# Sheet_V2.net
KiCad netlist of a schematic drawn in Altium Designer
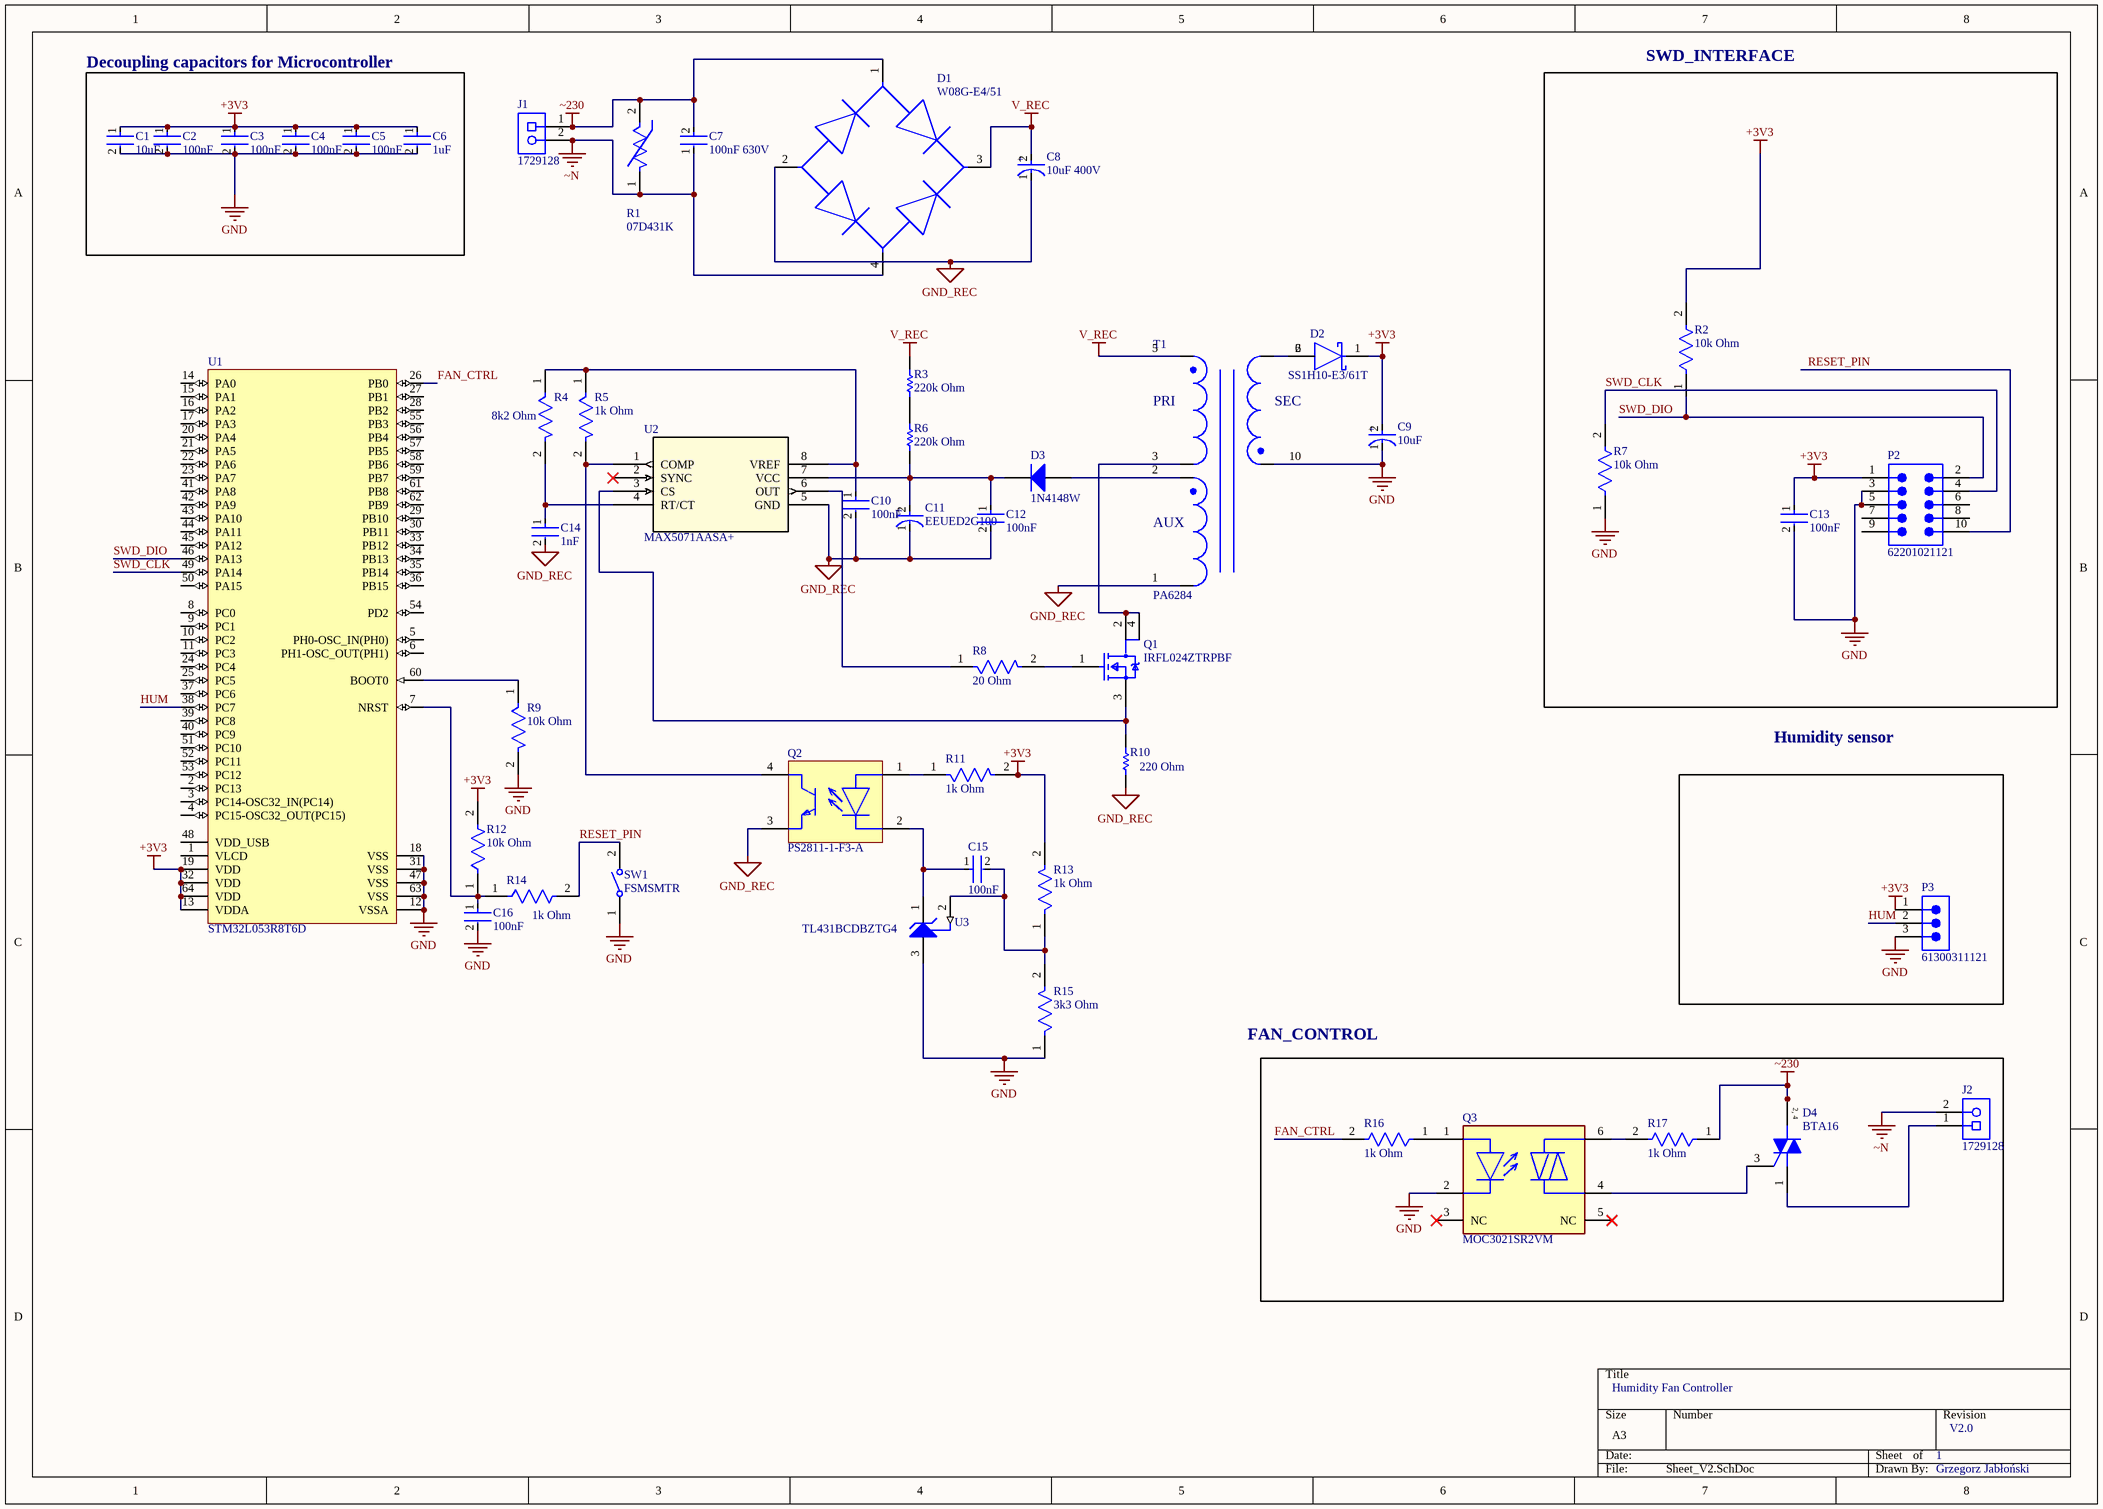
[diagram p0: Sheet_V2.SchDoc]

(export (version "E")
  (design (tool "Eeschema 10.0.6"))
  (components
    (comp (ref "C1")
      (value "10uF")
      (footprint "FP-CC0805-0_85-MFG")
      (description "CAP CER 0.1UF 50V X7R 0805")
      (fields (field (name "TOLERANCE") "0.1") (field (name "MANUFACTURER PART NUMBER") "CC0805KRX7R9BB104"))
      (libsource (lib "Altium Content Vault") (part "11868f565c42a9108669ba33697ecf6"))
    )
    (comp (ref "C2")
      (value "100nF")
      (footprint "FP-CC0805-0_85-MFG")
      (description "CAP CER 0.1UF 50V X7R 0805")
      (fields (field (name "TOLERANCE") "0.1") (field (name "MANUFACTURER PART NUMBER") "CC0805KRX7R9BB104"))
      (libsource (lib "Altium Content Vault") (part "11868f565c42a9108669ba33697ecf6"))
    )
    (comp (ref "C3")
      (value "100nF")
      (footprint "FP-CC0805-0_85-MFG")
      (description "CAP CER 0.1UF 50V X7R 0805")
      (fields (field (name "TOLERANCE") "0.1") (field (name "MANUFACTURER PART NUMBER") "CC0805KRX7R9BB104"))
      (libsource (lib "Altium Content Vault") (part "11868f565c42a9108669ba33697ecf6"))
    )
    (comp (ref "C4")
      (value "100nF")
      (footprint "FP-CC0805-0_85-MFG")
      (description "CAP CER 0.1UF 50V X7R 0805")
      (fields (field (name "TOLERANCE") "0.1") (field (name "MANUFACTURER PART NUMBER") "CC0805KRX7R9BB104"))
      (libsource (lib "Altium Content Vault") (part "11868f565c42a9108669ba33697ecf6"))
    )
    (comp (ref "C5")
      (value "100nF")
      (footprint "FP-CC0805-0_85-MFG")
      (description "CAP CER 0.1UF 50V X7R 0805")
      (fields (field (name "TOLERANCE") "0.1") (field (name "MANUFACTURER PART NUMBER") "CC0805KRX7R9BB104"))
      (libsource (lib "Altium Content Vault") (part "11868f565c42a9108669ba33697ecf6"))
    )
    (comp (ref "C6")
      (value "1uF")
      (footprint "FP-CC0805-0_85-MFG")
      (description "CAP CER 0.1UF 50V X7R 0805")
      (fields (field (name "TOLERANCE") "0.1") (field (name "MANUFACTURER PART NUMBER") "CC0805KRX7R9BB104"))
      (libsource (lib "Altium Content Vault") (part "11868f565c42a9108669ba33697ecf6"))
    )
    (comp (ref "C7")
      (value "100nF 630V")
      (footprint "FP-BFC233620104-MFG")
      (description "CAP FILM 0.1UF 20% 630VDC RADIAL")
      (fields (field (name "VOLTAGE") "250V") (field (name "TOLERANCE") "20%"))
      (libsource (lib "Altium Content Vault") (part "236180d848d6139a670b325ea6854c9"))
    )
    (comp (ref "C8")
      (value "10uF 400V")
      (footprint "FP-RAD-TH-D_10_0_5-L_20_2-MFG")
      (description "Aluminum Electrolytic Capacitors (Radial Lead Type) 10uF ±20% 400V")
      (fields (field (name "VOLTAGE") "400V") (field (name "TOLERANCE") "20%"))
      (libsource (lib "Altium Content Vault") (part "203bc49f2ac43e59fd269a8c329ed05"))
    )
    (comp (ref "C9")
      (value "10uF")
      (footprint "FP-RAD-TH-D_6_3_0_5-L_7_1-MFG")
      (description "Aluminum Electrolytic Capacitors (Radial Lead Type) 15uF ±20% 35V")
      (fields (field (name "TOLERANCE") "20%") (field (name "VOLTAGE") "35V"))
      (libsource (lib "Altium Content Vault") (part "a00bbbee19879c290e62620ae7e47b1"))
    )
    (comp (ref "C10")
      (value "100nF")
      (footprint "FP-CC0805-0_85-MFG")
      (description "CAP CER 0.1UF 50V X7R 0805")
      (fields (field (name "TOLERANCE") "0.1") (field (name "MANUFACTURER PART NUMBER") "CC0805KRX7R9BB104"))
      (libsource (lib "Altium Content Vault") (part "11868f565c42a9108669ba33697ecf6"))
    )
    (comp (ref "C11")
      (value "EEUED2G100")
      (footprint "FP-RAD-TH-D_10_0_5-L_20_2-MFG")
      (description "Aluminum Electrolytic Capacitors (Radial Lead Type) 10uF ±20% 400V")
      (fields (field (name "VOLTAGE") "400V") (field (name "TOLERANCE") "20%"))
      (libsource (lib "Altium Content Vault") (part "203bc49f2ac43e59fd269a8c329ed05"))
    )
    (comp (ref "C12")
      (value "100nF")
      (footprint "FP-CC0805-0_85-MFG")
      (description "CAP CER 0.1UF 50V X7R 0805")
      (fields (field (name "TOLERANCE") "0.1") (field (name "MANUFACTURER PART NUMBER") "CC0805KRX7R9BB104"))
      (libsource (lib "Altium Content Vault") (part "11868f565c42a9108669ba33697ecf6"))
    )
    (comp (ref "C13")
      (value "100nF")
      (footprint "FP-CC0805-0_85-MFG")
      (description "CAP CER 0.1UF 50V X7R 0805")
      (fields (field (name "TOLERANCE") "0.1") (field (name "MANUFACTURER PART NUMBER") "CC0805KRX7R9BB104"))
      (libsource (lib "Altium Content Vault") (part "11868f565c42a9108669ba33697ecf6"))
    )
    (comp (ref "C14")
      (value "1nF")
      (footprint "FP-CC0805-0_85-MFG")
      (description "CAP CER 0.1UF 50V X7R 0805")
      (fields (field (name "TOLERANCE") "0.1") (field (name "MANUFACTURER PART NUMBER") "CC0805KRX7R9BB104"))
      (libsource (lib "Altium Content Vault") (part "11868f565c42a9108669ba33697ecf6"))
    )
    (comp (ref "C15")
      (value "100nF")
      (footprint "FP-CC0805-0_85-MFG")
      (description "CAP CER 0.1UF 50V X7R 0805")
      (fields (field (name "TOLERANCE") "0.1") (field (name "MANUFACTURER PART NUMBER") "CC0805KRX7R9BB104"))
      (libsource (lib "Altium Content Vault") (part "11868f565c42a9108669ba33697ecf6"))
    )
    (comp (ref "C16")
      (value "100nF")
      (footprint "FP-CC0805-0_85-MFG")
      (description "CAP CER 0.1UF 50V X7R 0805")
      (fields (field (name "TOLERANCE") "0.1") (field (name "MANUFACTURER PART NUMBER") "CC0805KRX7R9BB104"))
      (libsource (lib "Altium Content Vault") (part "11868f565c42a9108669ba33697ecf6"))
    )
    (comp (ref "D1")
      (value "W08G-E4/51")
      (footprint "FP-WOG-MFG")
      (description "W08G-E4/51 Diode Rectifier Bridge Single 800V 1.5A 4-Pin Case WOG Bulk")
      (libsource (lib "Altium Content Vault") (part "7f679ecdc54638986ed3433d0c5b104"))
    )
    (comp (ref "D2")
      (value "SS1H10-E3/61T")
      (footprint "FP-95400-MFG")
      (description "DIODE SCHOTTKY 100V 1A DO214AC")
      (fields
        (field (name "OCTOPART") "https://octopart.com/ss1h10-e3%2F61t-vishay-39552861")
        (field (name "MANUFACTURER") "Vishay")
      )
      (libsource (lib "Altium Content Vault") (part "1d6ec82d83fb6aee721767c19dac4b9"))
    )
    (comp (ref "D3")
      (value "1N4148W")
      (footprint "DIOD-SOD123-2_V")
      (description "Fast Switching Diode, 100 V, 0.15 A, -65 to 150 degC, 2-Pin?SOD123, RoHS, Tape and Reel")
      (fields (field (name "MANUFACTURER") "DiodesIncorporated"))
      (libsource (lib "Altium Content Vault") (part "D-AK-2"))
    )
    (comp (ref "D4")
      (value "BTA16")
      (footprint "ONSC-SOT-223-4-318E-04_V")
      (fields (field (name "MANUFACTURER") "On Semiconductor") (field (name "PARTNUMBER") "Z0107MNT1G"))
      (libsource (lib "Altium Content Vault") (part "ONSC-TRIAC-MT1MT2GMT2-4"))
    )
    (comp (ref "J1")
      (value "1729128")
      (footprint "PHOE-1729128-2_V")
      (description "PCB Terminal Block, 13.5 A, 400 V, 2-Pin THD, RoHS, Bulk")
      (fields (field (name "MANUFACTURER") "Phoenix Contact"))
      (libsource (lib "") (part "CN-2P-F-R2_1"))
    )
    (comp (ref "J2")
      (value "1729128")
      (footprint "PHOE-1729128-2_V")
      (description "PCB Terminal Block, 13.5 A, 400 V, 2-Pin THD, RoHS, Bulk")
      (fields (field (name "MANUFACTURER") "Phoenix Contact"))
      (libsource (lib "Altium Content Vault") (part "CN-2P-F-R2"))
    )
    (comp (ref "P2")
      (value "62201021121")
      (footprint "62201021121")
      (libsource (lib "Altium Content Vault") (part "Header_Male_2R_10P"))
    )
    (comp (ref "P3")
      (value "61300311121")
      (footprint "61300311121")
      (libsource (lib "Altium Content Vault") (part "Header_Male_1R_03P"))
    )
    (comp (ref "Q1")
      (value "IRFL024ZTRPBF")
      (footprint "FP-PG-SOT223-3-MFG")
      (description "MOSFET N-CH 55V 5.1A SOT223")
      (libsource (lib "Altium Content Vault") (part "c6745a01100a3e91667466909d2f9ef"))
    )
    (comp (ref "Q2")
      (value "PS2811-1-F3-A")
      (footprint "SOP127P700X210_HS-5_SO4-Opto2_N")
      (description "Optocoupler DC-IN 1-CH Transistor DC-OUT 4-Pin SSOP Embossed T/R")
      (libsource (lib "Altium Content Vault") (part "f4732c5a005c16655bf03302f8bd1cc"))
    )
    (comp (ref "Q3")
      (value "MOC3021SR2VM")
      (footprint "FP-646BY-MFG")
      (description "MOC3021SR2VM Triac Driver Output Optocoupler, 6-Pin DIP 400V Random Phase")
      (libsource (lib "Altium Content Vault") (part "315d33d7a3de83856d3bd334bf87c2f"))
    )
    (comp (ref "R1")
      (value "07D431K")
      (footprint "FP-B72207S0110K101-MFG")
      (description "VARISTOR 18V 250A DISC 7MM")
      (fields
        (field (name "MANUFACTURER") "EPCOS")
        (field (name "MANUFACTURER PART NUMBER") "B72207S0110K101")
      )
      (libsource (lib "Altium Content Vault") (part "78a88060d5b7b043d6e48adc4284376"))
    )
    (comp (ref "R2")
      (value "10k Ohm")
      (footprint "FP-RMCF0805-MFG")
      (description "RES 0 OHM JUMPER 1/8W 0805")
      (libsource (lib "Altium Content Vault") (part "1029c3af85768c4190bb7ad29bc67b5"))
    )
    (comp (ref "R3")
      (value "220k Ohm")
      (footprint "RESC3216X70X50NL20T25")
      (fields (field (name "PART NUMBER") "ERA8AEB204V") (field (name "MANUFACTURER") "Panasonic"))
      (libsource (lib "Altium Content Vault") (part "RES"))
    )
    (comp (ref "R4")
      (value "8k2 Ohm")
      (footprint "FP-RMCF0805-MFG")
      (description "RES 0 OHM JUMPER 1/8W 0805")
      (libsource (lib "Altium Content Vault") (part "1029c3af85768c4190bb7ad29bc67b5"))
    )
    (comp (ref "R5")
      (value "1k Ohm")
      (footprint "FP-RMCF0805-MFG")
      (description "RES 0 OHM JUMPER 1/8W 0805")
      (libsource (lib "Altium Content Vault") (part "1029c3af85768c4190bb7ad29bc67b5"))
    )
    (comp (ref "R6")
      (value "220k Ohm")
      (footprint "RESC3216X70X50NL20T25")
      (fields (field (name "PART NUMBER") "ERA8AEB204V") (field (name "MANUFACTURER") "Panasonic"))
      (libsource (lib "Altium Content Vault") (part "RES"))
    )
    (comp (ref "R7")
      (value "10k Ohm")
      (footprint "FP-RMCF0805-MFG")
      (description "RES 0 OHM JUMPER 1/8W 0805")
      (libsource (lib "Altium Content Vault") (part "1029c3af85768c4190bb7ad29bc67b5"))
    )
    (comp (ref "R8")
      (value "20 Ohm")
      (footprint "FP-RMCF0805-MFG")
      (description "RES 0 OHM JUMPER 1/8W 0805")
      (libsource (lib "Altium Content Vault") (part "1029c3af85768c4190bb7ad29bc67b5"))
    )
    (comp (ref "R9")
      (value "10k Ohm")
      (footprint "FP-RMCF0805-MFG")
      (description "RES 0 OHM JUMPER 1/8W 0805")
      (libsource (lib "Altium Content Vault") (part "1029c3af85768c4190bb7ad29bc67b5"))
    )
    (comp (ref "R10")
      (value "220 Ohm")
      (footprint "RESC3216X70X50NL05T20")
      (fields (field (name "MANUFACTURER") "Panasonic") (field (name "PART NUMBER") "ERJ8ENF1200V"))
      (libsource (lib "Altium Content Vault") (part "RES"))
    )
    (comp (ref "R11")
      (value "1k Ohm")
      (footprint "FP-RMCF0805-MFG")
      (description "RES 0 OHM JUMPER 1/8W 0805")
      (libsource (lib "Altium Content Vault") (part "1029c3af85768c4190bb7ad29bc67b5"))
    )
    (comp (ref "R12")
      (value "10k Ohm")
      (footprint "FP-RMCF0805-MFG")
      (description "RES 0 OHM JUMPER 1/8W 0805")
      (libsource (lib "Altium Content Vault") (part "1029c3af85768c4190bb7ad29bc67b5"))
    )
    (comp (ref "R13")
      (value "1k Ohm")
      (footprint "FP-RMCF0805-MFG")
      (description "RES 0 OHM JUMPER 1/8W 0805")
      (libsource (lib "Altium Content Vault") (part "1029c3af85768c4190bb7ad29bc67b5"))
    )
    (comp (ref "R14")
      (value "1k Ohm")
      (footprint "FP-RMCF0805-MFG")
      (description "RES 0 OHM JUMPER 1/8W 0805")
      (libsource (lib "Altium Content Vault") (part "1029c3af85768c4190bb7ad29bc67b5"))
    )
    (comp (ref "R15")
      (value "3k3 Ohm")
      (footprint "FP-RMCF0805-MFG")
      (description "RES 0 OHM JUMPER 1/8W 0805")
      (libsource (lib "Altium Content Vault") (part "1029c3af85768c4190bb7ad29bc67b5"))
    )
    (comp (ref "R16")
      (value "1k Ohm")
      (footprint "FP-RMCF0805-MFG")
      (description "RES 0 OHM JUMPER 1/8W 0805")
      (libsource (lib "Altium Content Vault") (part "1029c3af85768c4190bb7ad29bc67b5"))
    )
    (comp (ref "R17")
      (value "1k Ohm")
      (footprint "FP-RMCF0805-MFG")
      (description "RES 0 OHM JUMPER 1/8W 0805")
      (libsource (lib "Altium Content Vault") (part "1029c3af85768c4190bb7ad29bc67b5"))
    )
    (comp (ref "SW1")
      (value "FSMSMTR")
      (footprint "TECO-FSMSMTR_V")
      (description "FSMSM Push Button Switch, 50 mA, -35 to 85 degC, 2-Pin SMD, RoHS, Tape and Reel")
      (fields (field (name "MANUFACTURER") "TE Connectivity"))
      (libsource (lib "Altium Content Vault") (part "SW-SPST-2_C"))
    )
    (comp (ref "T1")
      (value "PA6284")
      (footprint "ALD")
      (description "PA6284 Flyback Transformer")
      (libsource (lib "PA6284") (part "PA6284"))
    )
    (comp (ref "U1")
      (value "STM32L053R8T6D")
      (footprint "STM-LQFP64_L")
      (libsource (lib "Altium Content Vault") (part "MC-ARM-STM32L053-LQFP64"))
    )
    (comp (ref "U2")
      (value "MAX5071AASA+")
      (footprint "21-0041_S8+4_MXM")
      (description "No Description Available")
      (libsource (lib "MAX5071AASA&plus_") (part "MAX5071AASA+"))
    )
    (comp (ref "U3")
      (value "TL431BCDBZTG4")
      (footprint "TI-DBZ3_N")
      (fields (field (name "MANUFACTURER") "Texas Instruments"))
      (libsource (lib "Altium Content Vault") (part "TI-TL431BDBZ3"))
    )
  )
  (nets
    (net (code "1") (name "+3V3") (class "Default")
      (node (ref "C1") (pin "1") (pinfunction "1_1") (pintype "passive"))
      (node (ref "C13") (pin "1") (pinfunction "1_1") (pintype "passive"))
      (node (ref "C2") (pin "1") (pinfunction "1_1") (pintype "passive"))
      (node (ref "C3") (pin "1") (pinfunction "1_1") (pintype "passive"))
      (node (ref "C4") (pin "1") (pinfunction "1_1") (pintype "passive"))
      (node (ref "C5") (pin "1") (pinfunction "1_1") (pintype "passive"))
      (node (ref "C6") (pin "1") (pinfunction "1_1") (pintype "passive"))
      (node (ref "C9") (pin "2") (pinfunction "A_2") (pintype "passive"))
      (node (ref "D2") (pin "1") (pinfunction "C_1") (pintype "passive"))
      (node (ref "P2") (pin "1") (pinfunction "1_1") (pintype "passive"))
      (node (ref "P3") (pin "1") (pinfunction "1_1") (pintype "passive"))
      (node (ref "R11") (pin "2") (pinfunction "2_2") (pintype "passive"))
      (node (ref "R12") (pin "2") (pinfunction "2_2") (pintype "passive"))
      (node (ref "R13") (pin "2") (pinfunction "2_2") (pintype "passive"))
      (node (ref "R2") (pin "2") (pinfunction "2_2") (pintype "passive"))
      (node (ref "U1") (pin "13") (pinfunction "VDDA_13") (pintype "power_in"))
      (node (ref "U1") (pin "19") (pinfunction "VDD_19") (pintype "power_in"))
      (node (ref "U1") (pin "32") (pinfunction "VDD_32") (pintype "power_in"))
      (node (ref "U1") (pin "64") (pinfunction "VDD_64") (pintype "power_in"))
    )
    (net (code "2") (name "/FAN_CTRL") (class "Default")
      (node (ref "R16") (pin "2") (pinfunction "2_2") (pintype "passive"))
      (node (ref "U1") (pin "26") (pinfunction "PB0_26") (pintype "bidirectional"))
    )
    (net (code "3") (name "/HUM") (class "Default")
      (node (ref "P3") (pin "2") (pinfunction "2_2") (pintype "passive"))
      (node (ref "U1") (pin "38") (pinfunction "PC7_38") (pintype "bidirectional"))
    )
    (net (code "4") (name "/RESET_PIN") (class "Default")
      (node (ref "P2") (pin "10") (pinfunction "10_10") (pintype "passive"))
      (node (ref "R14") (pin "2") (pinfunction "2_2") (pintype "passive"))
      (node (ref "SW1") (pin "2") (pinfunction "2_2") (pintype "passive"))
    )
    (net (code "5") (name "/SWD_CLK") (class "Default")
      (node (ref "P2") (pin "4") (pinfunction "4_4") (pintype "passive"))
      (node (ref "R7") (pin "2") (pinfunction "2_2") (pintype "passive"))
      (node (ref "U1") (pin "49") (pinfunction "PA14_49") (pintype "bidirectional"))
    )
    (net (code "6") (name "/SWD_DIO") (class "Default")
      (node (ref "P2") (pin "2") (pinfunction "2_2") (pintype "passive"))
      (node (ref "R2") (pin "1") (pinfunction "1_1") (pintype "passive"))
      (node (ref "U1") (pin "46") (pinfunction "PA13_46") (pintype "bidirectional"))
    )
    (net (code "7") (name "GND") (class "Default")
      (node (ref "C1") (pin "2") (pinfunction "2_2") (pintype "passive"))
      (node (ref "C13") (pin "2") (pinfunction "2_2") (pintype "passive"))
      (node (ref "C16") (pin "2") (pinfunction "2_2") (pintype "passive"))
      (node (ref "C2") (pin "2") (pinfunction "2_2") (pintype "passive"))
      (node (ref "C3") (pin "2") (pinfunction "2_2") (pintype "passive"))
      (node (ref "C4") (pin "2") (pinfunction "2_2") (pintype "passive"))
      (node (ref "C5") (pin "2") (pinfunction "2_2") (pintype "passive"))
      (node (ref "C6") (pin "2") (pinfunction "2_2") (pintype "passive"))
      (node (ref "C9") (pin "1") (pinfunction "C_1") (pintype "passive"))
      (node (ref "P2") (pin "3") (pinfunction "3_3") (pintype "passive"))
      (node (ref "P2") (pin "5") (pinfunction "5_5") (pintype "passive"))
      (node (ref "P3") (pin "3") (pinfunction "3_3") (pintype "passive"))
      (node (ref "Q3") (pin "2") (pinfunction "C_2") (pintype "passive"))
      (node (ref "R15") (pin "1") (pinfunction "1_1") (pintype "passive"))
      (node (ref "R7") (pin "1") (pinfunction "1_1") (pintype "passive"))
      (node (ref "R9") (pin "2") (pinfunction "2_2") (pintype "passive"))
      (node (ref "SW1") (pin "1") (pinfunction "1_1") (pintype "passive"))
      (node (ref "T1") (pin "10") (pinfunction "10_10") (pintype "passive"))
      (node (ref "U1") (pin "12") (pinfunction "VSSA_12") (pintype "power_in"))
      (node (ref "U1") (pin "18") (pinfunction "VSS_18") (pintype "power_in"))
      (node (ref "U1") (pin "31") (pinfunction "VSS_31") (pintype "power_in"))
      (node (ref "U1") (pin "47") (pinfunction "VSS_47") (pintype "power_in"))
      (node (ref "U1") (pin "63") (pinfunction "VSS_63") (pintype "power_in"))
      (node (ref "U3") (pin "3") (pinfunction "ANODE_3") (pintype "passive"))
    )
    (net (code "8") (name "GND_REC") (class "Default")
      (node (ref "C10") (pin "2") (pinfunction "2_2") (pintype "passive"))
      (node (ref "C11") (pin "1") (pinfunction "C_1") (pintype "passive"))
      (node (ref "C12") (pin "2") (pinfunction "2_2") (pintype "passive"))
      (node (ref "C14") (pin "2") (pinfunction "2_2") (pintype "passive"))
      (node (ref "C8") (pin "1") (pinfunction "C_1") (pintype "passive"))
      (node (ref "D1") (pin "2") (pinfunction "+_2") (pintype "passive"))
      (node (ref "Q2") (pin "3") (pinfunction "E_3") (pintype "passive"))
      (node (ref "R10") (pin "1") (pinfunction "1_1") (pintype "passive"))
      (node (ref "T1") (pin "1") (pinfunction "1_1") (pintype "passive"))
      (node (ref "U2") (pin "5") (pinfunction "GND_5") (pintype "power_in"))
    )
    (net (code "9") (name "Net-(C11-A)") (class "Default")
      (node (ref "C11") (pin "2") (pinfunction "A_2") (pintype "passive"))
      (node (ref "C12") (pin "1") (pinfunction "1_1") (pintype "passive"))
      (node (ref "D3") (pin "2") (pinfunction "K_2") (pintype "passive"))
      (node (ref "R6") (pin "1") (pinfunction "1_1") (pintype "passive"))
      (node (ref "U2") (pin "7") (pinfunction "VCC_7") (pintype "power_in"))
    )
    (net (code "10") (name "Net-(D2-A)") (class "Default")
      (node (ref "D2") (pin "2") (pinfunction "A_2") (pintype "passive"))
      (node (ref "T1") (pin "6") (pinfunction "6_6") (pintype "passive"))
    )
    (net (code "11") (name "Net-(D3-A)") (class "Default")
      (node (ref "D3") (pin "1") (pinfunction "A_1") (pintype "passive"))
      (node (ref "T1") (pin "2") (pinfunction "2_2") (pintype "passive"))
    )
    (net (code "12") (name "Net-(D4-G)") (class "Default")
      (node (ref "D4") (pin "3") (pinfunction "G_3") (pintype "passive"))
      (node (ref "Q3") (pin "4") (pinfunction "1_MAIN_TERM_4") (pintype "passive"))
    )
    (net (code "13") (name "Net-(D4-MT1)") (class "Default")
      (node (ref "D4") (pin "1") (pinfunction "MT1_1") (pintype "passive"))
      (node (ref "J2") (pin "1") (pinfunction "1_1") (pintype "passive"))
    )
    (net (code "14") (name "Net-(Q1-DRAIN-Pad2)") (class "Default")
      (node (ref "Q1") (pin "2") (pinfunction "DRAIN_2") (pintype "passive"))
      (node (ref "Q1") (pin "4") (pinfunction "DRAIN_4") (pintype "passive"))
      (node (ref "T1") (pin "3") (pinfunction "3_3") (pintype "passive"))
    )
    (net (code "15") (name "Net-(Q1-GATE)") (class "Default")
      (node (ref "Q1") (pin "1") (pinfunction "GATE_1") (pintype "passive"))
      (node (ref "R8") (pin "2") (pinfunction "2_2") (pintype "passive"))
    )
    (net (code "16") (name "Net-(Q1-SOURCE)") (class "Default")
      (node (ref "Q1") (pin "3") (pinfunction "SOURCE_3") (pintype "passive"))
      (node (ref "R10") (pin "2") (pinfunction "2_2") (pintype "passive"))
      (node (ref "U2") (pin "3") (pinfunction "CS_3") (pintype "input"))
    )
    (net (code "17") (name "Net-(Q2-A)") (class "Default")
      (node (ref "Q2") (pin "1") (pinfunction "A_1") (pintype "passive"))
      (node (ref "R11") (pin "1") (pinfunction "1_1") (pintype "passive"))
    )
    (net (code "18") (name "Net-(Q3-2_MAIN_TERM)") (class "Default")
      (node (ref "Q3") (pin "6") (pinfunction "2_MAIN_TERM_6") (pintype "passive"))
      (node (ref "R17") (pin "2") (pinfunction "2_2") (pintype "passive"))
    )
    (net (code "19") (name "Net-(Q3-A)") (class "Default")
      (node (ref "Q3") (pin "1") (pinfunction "A_1") (pintype "passive"))
      (node (ref "R16") (pin "1") (pinfunction "1_1") (pintype "passive"))
    )
    (net (code "20") (name "Net-(R3-Pad1)") (class "Default")
      (node (ref "R3") (pin "1") (pinfunction "1_1") (pintype "passive"))
      (node (ref "R6") (pin "2") (pinfunction "2_2") (pintype "passive"))
    )
    (net (code "21") (name "Net-(U1-BOOT0)") (class "Default")
      (node (ref "R9") (pin "1") (pinfunction "1_1") (pintype "passive"))
      (node (ref "U1") (pin "60") (pinfunction "BOOT0_60") (pintype "input"))
    )
    (net (code "22") (name "Net-(U1-NRST)") (class "Default")
      (node (ref "C16") (pin "1") (pinfunction "1_1") (pintype "passive"))
      (node (ref "R12") (pin "1") (pinfunction "1_1") (pintype "passive"))
      (node (ref "R14") (pin "1") (pinfunction "1_1") (pintype "passive"))
      (node (ref "U1") (pin "7") (pinfunction "NRST_7") (pintype "bidirectional"))
    )
    (net (code "23") (name "Net-(U2-COMP)") (class "Default")
      (node (ref "Q2") (pin "4") (pinfunction "C_4") (pintype "passive"))
      (node (ref "R5") (pin "2") (pinfunction "2_2") (pintype "passive"))
      (node (ref "U2") (pin "1") (pinfunction "COMP_1") (pintype "output"))
    )
    (net (code "24") (name "Net-(U2-OUT)") (class "Default")
      (node (ref "R8") (pin "1") (pinfunction "1_1") (pintype "passive"))
      (node (ref "U2") (pin "6") (pinfunction "OUT_6") (pintype "output"))
    )
    (net (code "25") (name "Net-(U2-RT{slash}CT)") (class "Default")
      (node (ref "C14") (pin "1") (pinfunction "1_1") (pintype "passive"))
      (node (ref "R4") (pin "2") (pinfunction "2_2") (pintype "passive"))
      (node (ref "U2") (pin "4") (pinfunction "RT/CT_4") (pintype "passive"))
    )
    (net (code "26") (name "Net-(U2-VREF)") (class "Default")
      (node (ref "C10") (pin "1") (pinfunction "1_1") (pintype "passive"))
      (node (ref "R4") (pin "1") (pinfunction "1_1") (pintype "passive"))
      (node (ref "R5") (pin "1") (pinfunction "1_1") (pintype "passive"))
      (node (ref "U2") (pin "8") (pinfunction "VREF_8") (pintype "power_in"))
    )
    (net (code "27") (name "Net-(U3-CATHODE)") (class "Default")
      (node (ref "C15") (pin "1") (pinfunction "1_1") (pintype "passive"))
      (node (ref "Q2") (pin "2") (pinfunction "C_2") (pintype "passive"))
      (node (ref "U3") (pin "1") (pinfunction "CATHODE_1") (pintype "passive"))
    )
    (net (code "28") (name "Net-(U3-REF)") (class "Default")
      (node (ref "C15") (pin "2") (pinfunction "2_2") (pintype "passive"))
      (node (ref "R13") (pin "1") (pinfunction "1_1") (pintype "passive"))
      (node (ref "R15") (pin "2") (pinfunction "2_2") (pintype "passive"))
      (node (ref "U3") (pin "2") (pinfunction "REF_2") (pintype "input"))
    )
    (net (code "29") (name "V_REC") (class "Default")
      (node (ref "C8") (pin "2") (pinfunction "A_2") (pintype "passive"))
      (node (ref "D1") (pin "3") (pinfunction "-_3") (pintype "passive"))
      (node (ref "R3") (pin "2") (pinfunction "2_2") (pintype "passive"))
      (node (ref "T1") (pin "5") (pinfunction "5_5") (pintype "passive"))
    )
    (net (code "30") (name "unconnected-(P2-Pad6)") (class "Default")
      (node (ref "P2") (pin "6") (pinfunction "6_6") (pintype "passive"))
    )
    (net (code "31") (name "unconnected-(P2-Pad7)") (class "Default")
      (node (ref "P2") (pin "7") (pinfunction "7_7") (pintype "passive"))
    )
    (net (code "32") (name "unconnected-(P2-Pad8)") (class "Default")
      (node (ref "P2") (pin "8") (pinfunction "8_8") (pintype "passive"))
    )
    (net (code "33") (name "unconnected-(P2-Pad9)") (class "Default")
      (node (ref "P2") (pin "9") (pinfunction "9_9") (pintype "passive"))
    )
    (net (code "34") (name "unconnected-(Q3-NC-Pad3)") (class "Default")
      (node (ref "Q3") (pin "3") (pinfunction "NC_3") (pintype "passive+no_connect"))
    )
    (net (code "35") (name "unconnected-(Q3-NC-Pad5)") (class "Default")
      (node (ref "Q3") (pin "5") (pinfunction "NC_5") (pintype "passive+no_connect"))
    )
    (net (code "36") (name "unconnected-(U1-PA0-Pad14)") (class "Default")
      (node (ref "U1") (pin "14") (pinfunction "PA0_14") (pintype "bidirectional"))
    )
    (net (code "37") (name "unconnected-(U1-PA1-Pad15)") (class "Default")
      (node (ref "U1") (pin "15") (pinfunction "PA1_15") (pintype "bidirectional"))
    )
    (net (code "38") (name "unconnected-(U1-PA2-Pad16)") (class "Default")
      (node (ref "U1") (pin "16") (pinfunction "PA2_16") (pintype "bidirectional"))
    )
    (net (code "39") (name "unconnected-(U1-PA3-Pad17)") (class "Default")
      (node (ref "U1") (pin "17") (pinfunction "PA3_17") (pintype "bidirectional"))
    )
    (net (code "40") (name "unconnected-(U1-PA4-Pad20)") (class "Default")
      (node (ref "U1") (pin "20") (pinfunction "PA4_20") (pintype "bidirectional"))
    )
    (net (code "41") (name "unconnected-(U1-PA5-Pad21)") (class "Default")
      (node (ref "U1") (pin "21") (pinfunction "PA5_21") (pintype "bidirectional"))
    )
    (net (code "42") (name "unconnected-(U1-PA6-Pad22)") (class "Default")
      (node (ref "U1") (pin "22") (pinfunction "PA6_22") (pintype "bidirectional"))
    )
    (net (code "43") (name "unconnected-(U1-PA7-Pad23)") (class "Default")
      (node (ref "U1") (pin "23") (pinfunction "PA7_23") (pintype "bidirectional"))
    )
    (net (code "44") (name "unconnected-(U1-PA8-Pad41)") (class "Default")
      (node (ref "U1") (pin "41") (pinfunction "PA8_41") (pintype "bidirectional"))
    )
    (net (code "45") (name "unconnected-(U1-PA9-Pad42)") (class "Default")
      (node (ref "U1") (pin "42") (pinfunction "PA9_42") (pintype "bidirectional"))
    )
    (net (code "46") (name "unconnected-(U1-PA10-Pad43)") (class "Default")
      (node (ref "U1") (pin "43") (pinfunction "PA10_43") (pintype "bidirectional"))
    )
    (net (code "47") (name "unconnected-(U1-PA11-Pad44)") (class "Default")
      (node (ref "U1") (pin "44") (pinfunction "PA11_44") (pintype "bidirectional"))
    )
    (net (code "48") (name "unconnected-(U1-PA12-Pad45)") (class "Default")
      (node (ref "U1") (pin "45") (pinfunction "PA12_45") (pintype "bidirectional"))
    )
    (net (code "49") (name "unconnected-(U1-PA15-Pad50)") (class "Default")
      (node (ref "U1") (pin "50") (pinfunction "PA15_50") (pintype "bidirectional"))
    )
    (net (code "50") (name "unconnected-(U1-PB1-Pad27)") (class "Default")
      (node (ref "U1") (pin "27") (pinfunction "PB1_27") (pintype "bidirectional"))
    )
    (net (code "51") (name "unconnected-(U1-PB2-Pad28)") (class "Default")
      (node (ref "U1") (pin "28") (pinfunction "PB2_28") (pintype "bidirectional"))
    )
    (net (code "52") (name "unconnected-(U1-PB3-Pad55)") (class "Default")
      (node (ref "U1") (pin "55") (pinfunction "PB3_55") (pintype "bidirectional"))
    )
    (net (code "53") (name "unconnected-(U1-PB4-Pad56)") (class "Default")
      (node (ref "U1") (pin "56") (pinfunction "PB4_56") (pintype "bidirectional"))
    )
    (net (code "54") (name "unconnected-(U1-PB5-Pad57)") (class "Default")
      (node (ref "U1") (pin "57") (pinfunction "PB5_57") (pintype "bidirectional"))
    )
    (net (code "55") (name "unconnected-(U1-PB6-Pad58)") (class "Default")
      (node (ref "U1") (pin "58") (pinfunction "PB6_58") (pintype "bidirectional"))
    )
    (net (code "56") (name "unconnected-(U1-PB7-Pad59)") (class "Default")
      (node (ref "U1") (pin "59") (pinfunction "PB7_59") (pintype "bidirectional"))
    )
    (net (code "57") (name "unconnected-(U1-PB8-Pad61)") (class "Default")
      (node (ref "U1") (pin "61") (pinfunction "PB8_61") (pintype "bidirectional"))
    )
    (net (code "58") (name "unconnected-(U1-PB9-Pad62)") (class "Default")
      (node (ref "U1") (pin "62") (pinfunction "PB9_62") (pintype "bidirectional"))
    )
    (net (code "59") (name "unconnected-(U1-PB10-Pad29)") (class "Default")
      (node (ref "U1") (pin "29") (pinfunction "PB10_29") (pintype "bidirectional"))
    )
    (net (code "60") (name "unconnected-(U1-PB11-Pad30)") (class "Default")
      (node (ref "U1") (pin "30") (pinfunction "PB11_30") (pintype "bidirectional"))
    )
    (net (code "61") (name "unconnected-(U1-PB12-Pad33)") (class "Default")
      (node (ref "U1") (pin "33") (pinfunction "PB12_33") (pintype "bidirectional"))
    )
    (net (code "62") (name "unconnected-(U1-PB13-Pad34)") (class "Default")
      (node (ref "U1") (pin "34") (pinfunction "PB13_34") (pintype "bidirectional"))
    )
    (net (code "63") (name "unconnected-(U1-PB14-Pad35)") (class "Default")
      (node (ref "U1") (pin "35") (pinfunction "PB14_35") (pintype "bidirectional"))
    )
    (net (code "64") (name "unconnected-(U1-PB15-Pad36)") (class "Default")
      (node (ref "U1") (pin "36") (pinfunction "PB15_36") (pintype "bidirectional"))
    )
    (net (code "65") (name "unconnected-(U1-PC0-Pad8)") (class "Default")
      (node (ref "U1") (pin "8") (pinfunction "PC0_8") (pintype "bidirectional"))
    )
    (net (code "66") (name "unconnected-(U1-PC1-Pad9)") (class "Default")
      (node (ref "U1") (pin "9") (pinfunction "PC1_9") (pintype "bidirectional"))
    )
    (net (code "67") (name "unconnected-(U1-PC2-Pad10)") (class "Default")
      (node (ref "U1") (pin "10") (pinfunction "PC2_10") (pintype "bidirectional"))
    )
    (net (code "68") (name "unconnected-(U1-PC3-Pad11)") (class "Default")
      (node (ref "U1") (pin "11") (pinfunction "PC3_11") (pintype "bidirectional"))
    )
    (net (code "69") (name "unconnected-(U1-PC4-Pad24)") (class "Default")
      (node (ref "U1") (pin "24") (pinfunction "PC4_24") (pintype "bidirectional"))
    )
    (net (code "70") (name "unconnected-(U1-PC5-Pad25)") (class "Default")
      (node (ref "U1") (pin "25") (pinfunction "PC5_25") (pintype "bidirectional"))
    )
    (net (code "71") (name "unconnected-(U1-PC6-Pad37)") (class "Default")
      (node (ref "U1") (pin "37") (pinfunction "PC6_37") (pintype "bidirectional"))
    )
    (net (code "72") (name "unconnected-(U1-PC8-Pad39)") (class "Default")
      (node (ref "U1") (pin "39") (pinfunction "PC8_39") (pintype "bidirectional"))
    )
    (net (code "73") (name "unconnected-(U1-PC9-Pad40)") (class "Default")
      (node (ref "U1") (pin "40") (pinfunction "PC9_40") (pintype "bidirectional"))
    )
    (net (code "74") (name "unconnected-(U1-PC10-Pad51)") (class "Default")
      (node (ref "U1") (pin "51") (pinfunction "PC10_51") (pintype "bidirectional"))
    )
    (net (code "75") (name "unconnected-(U1-PC11-Pad52)") (class "Default")
      (node (ref "U1") (pin "52") (pinfunction "PC11_52") (pintype "bidirectional"))
    )
    (net (code "76") (name "unconnected-(U1-PC12-Pad53)") (class "Default")
      (node (ref "U1") (pin "53") (pinfunction "PC12_53") (pintype "bidirectional"))
    )
    (net (code "77") (name "unconnected-(U1-PC13-Pad2)") (class "Default")
      (node (ref "U1") (pin "2") (pinfunction "PC13_2") (pintype "bidirectional"))
    )
    (net (code "78") (name "unconnected-(U1-PC14-OSC32_IN(PC14)-Pad3)") (class "Default")
      (node (ref "U1") (pin "3") (pinfunction "PC14-OSC32_IN(PC14)_3") (pintype "bidirectional"))
    )
    (net (code "79") (name "unconnected-(U1-PC15-OSC32_OUT(PC15)-Pad4)") (class "Default")
      (node (ref "U1") (pin "4") (pinfunction "PC15-OSC32_OUT(PC15)_4") (pintype "bidirectional"))
    )
    (net (code "80") (name "unconnected-(U1-PD2-Pad54)") (class "Default")
      (node (ref "U1") (pin "54") (pinfunction "PD2_54") (pintype "bidirectional"))
    )
    (net (code "81") (name "unconnected-(U1-PH0-OSC_IN(PH0)-Pad5)") (class "Default")
      (node (ref "U1") (pin "5") (pinfunction "PH0-OSC_IN(PH0)_5") (pintype "bidirectional"))
    )
    (net (code "82") (name "unconnected-(U1-PH1-OSC_OUT(PH1)-Pad6)") (class "Default")
      (node (ref "U1") (pin "6") (pinfunction "PH1-OSC_OUT(PH1)_6") (pintype "bidirectional"))
    )
    (net (code "83") (name "unconnected-(U1-VDD_USB-Pad48)") (class "Default")
      (node (ref "U1") (pin "48") (pinfunction "VDD_USB_48") (pintype "power_in"))
    )
    (net (code "84") (name "unconnected-(U1-VLCD-Pad1)") (class "Default")
      (node (ref "U1") (pin "1") (pinfunction "VLCD_1") (pintype "power_in"))
    )
    (net (code "85") (name "unconnected-(U2-SYNC-Pad2)") (class "Default")
      (node (ref "U2") (pin "2") (pinfunction "SYNC_2") (pintype "input+no_connect"))
    )
    (net (code "86") (name "~230") (class "Default")
      (node (ref "C7") (pin "2") (pinfunction "2_2") (pintype "passive"))
      (node (ref "D1") (pin "1") (pinfunction "1_~_1") (pintype "passive"))
      (node (ref "D4") (pin "2") (pinfunction "MT2_2") (pintype "passive"))
      (node (ref "D4") (pin "4") (pinfunction "MT2_4") (pintype "passive"))
      (node (ref "J1") (pin "1") (pinfunction "1_1") (pintype "passive"))
      (node (ref "R1") (pin "2") (pinfunction "2_2") (pintype "passive"))
      (node (ref "R17") (pin "1") (pinfunction "1_1") (pintype "passive"))
    )
    (net (code "87") (name "~N") (class "Default")
      (node (ref "C7") (pin "1") (pinfunction "1_1") (pintype "passive"))
      (node (ref "D1") (pin "4") (pinfunction "2_~_4") (pintype "passive"))
      (node (ref "J1") (pin "2") (pinfunction "2_2") (pintype "passive"))
      (node (ref "J2") (pin "2") (pinfunction "2_2") (pintype "passive"))
      (node (ref "R1") (pin "1") (pinfunction "1_1") (pintype "passive"))
    )
  )
)
